# Zio_Qwiic_GPS_Module.net
KiCad netlist of a schematic drawn in EAGLE
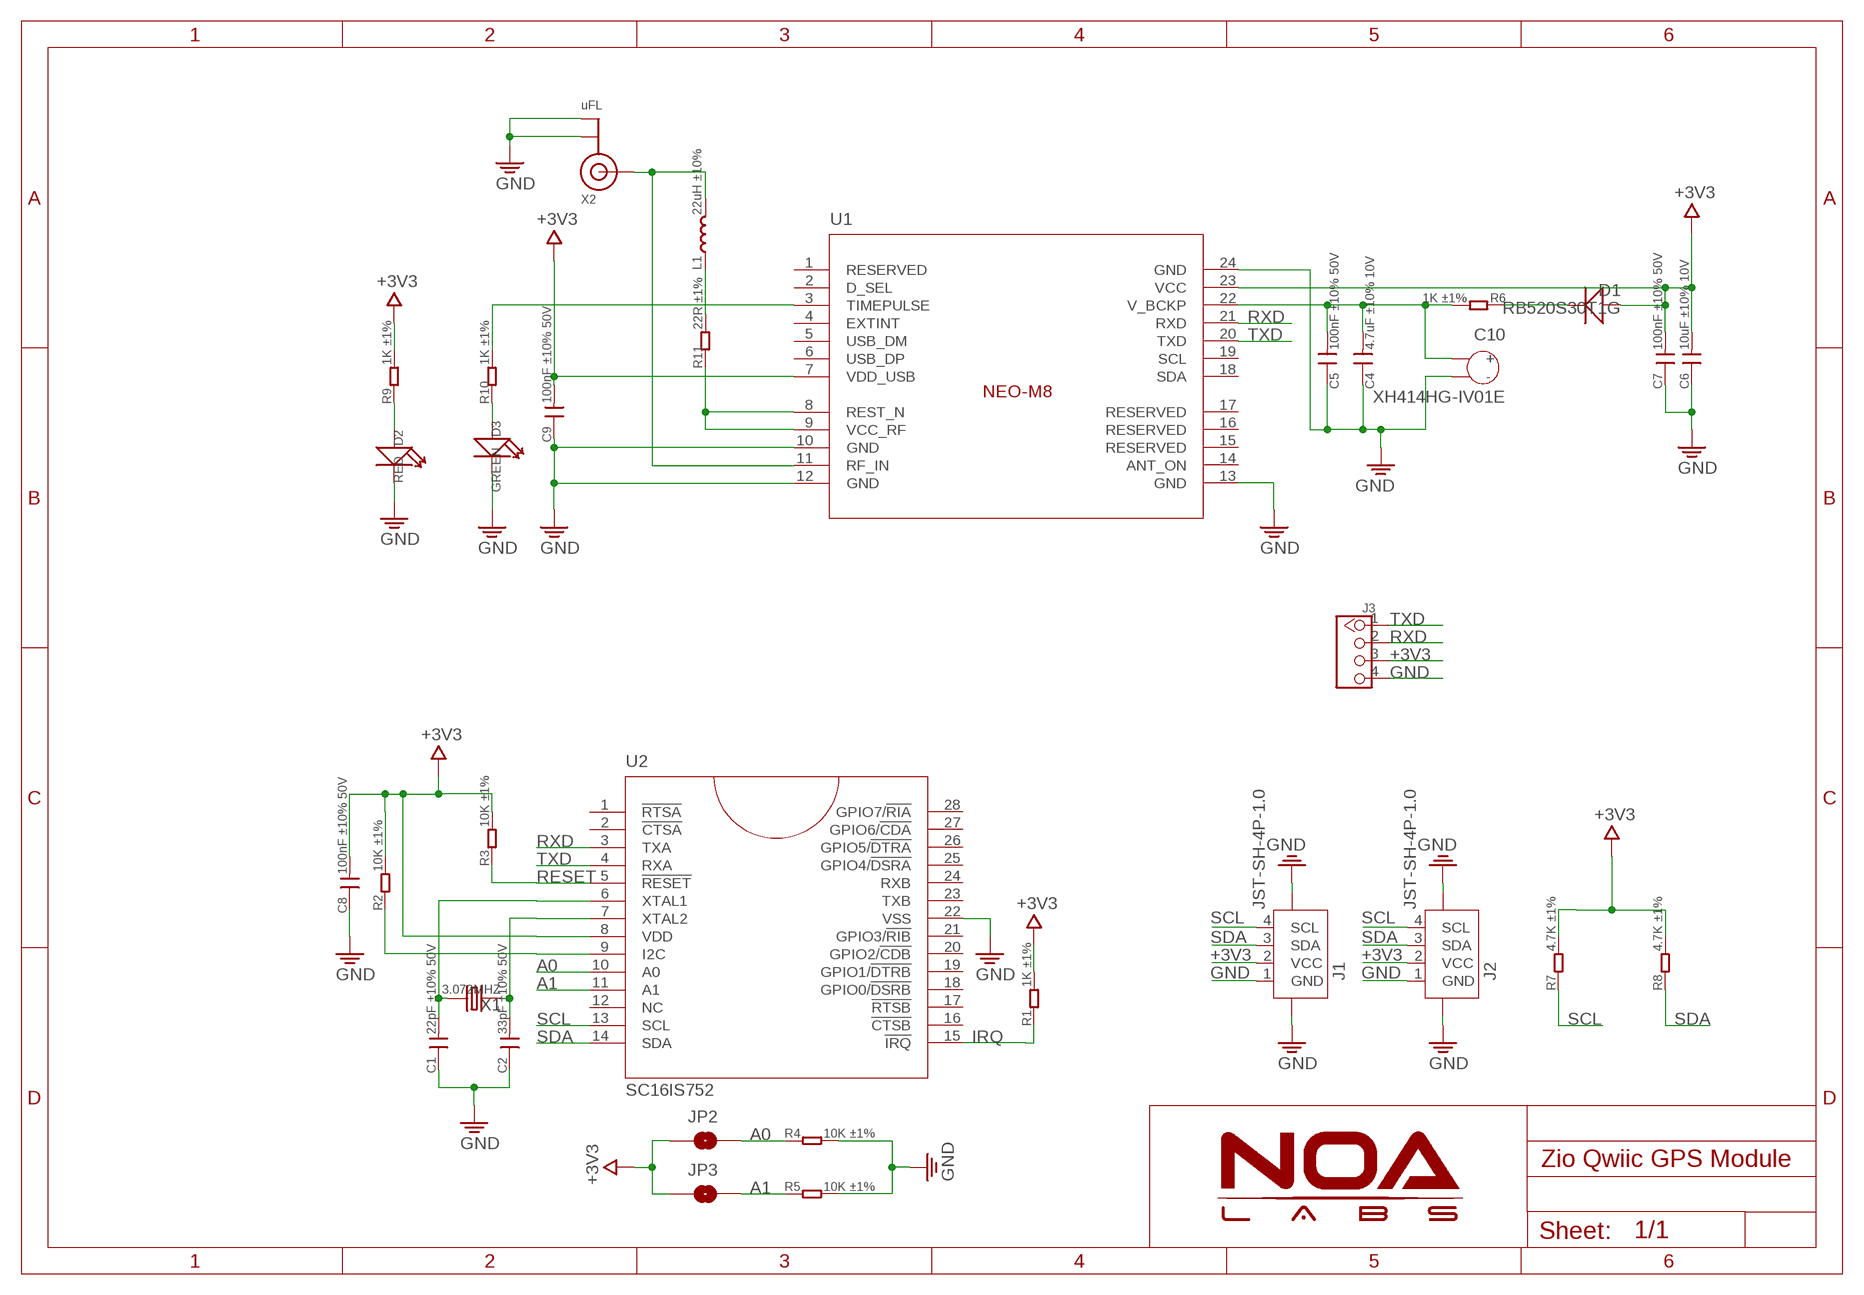
[diagram p0: schematic, sheet 1]

(export (version "E")
  (design (tool "Eeschema 10.0.6"))
  (components
    (comp (ref "C1")
      (value "22pF ±10% 50V")
      (footprint "eagle-import:C0603")
      (libsource (lib "eagle-import") (part "C-0603"))
    )
    (comp (ref "C2")
      (value "33pF ±10% 50V")
      (footprint "eagle-import:C0603")
      (libsource (lib "eagle-import") (part "C-0603"))
    )
    (comp (ref "C4")
      (value "4.7uF ±10% 10V")
      (footprint "eagle-import:C0603")
      (libsource (lib "eagle-import") (part "C-0603"))
    )
    (comp (ref "C5")
      (value "100nF ±10% 50V")
      (footprint "eagle-import:C0603")
      (libsource (lib "eagle-import") (part "C-0603"))
    )
    (comp (ref "C6")
      (value "10uF ±10% 10V")
      (footprint "eagle-import:C0603")
      (libsource (lib "eagle-import") (part "C-0603"))
    )
    (comp (ref "C7")
      (value "100nF ±10% 50V")
      (footprint "eagle-import:C0603")
      (libsource (lib "eagle-import") (part "C-0603"))
    )
    (comp (ref "C8")
      (value "100nF ±10% 50V")
      (footprint "eagle-import:C0603")
      (libsource (lib "eagle-import") (part "C-0603"))
    )
    (comp (ref "C9")
      (value "100nF ±10% 50V")
      (footprint "eagle-import:C0603")
      (libsource (lib "eagle-import") (part "C-0603"))
    )
    (comp (ref "C10")
      (value "XH414HG-IV01E")
      (footprint "eagle-import:XH414HG-IV01E")
      (libsource (lib "eagle-import") (part "XH414HG-IV01E"))
    )
    (comp (ref "D1")
      (value "RB520S30T1G")
      (footprint "eagle-import:SOD523")
      (libsource (lib "eagle-import") (part "D-0603"))
    )
    (comp (ref "D2")
      (value "RED")
      (footprint "eagle-import:LED-0603")
      (libsource (lib "eagle-import") (part "LED'0603'"))
    )
    (comp (ref "D3")
      (value "GREEN")
      (footprint "eagle-import:LED-0603")
      (libsource (lib "eagle-import") (part "LED'0603'"))
    )
    (comp (ref "J1")
      (value "JST-SH-4P-1.0")
      (footprint "eagle-import:JST-SH-4P")
      (libsource (lib "eagle-import") (part "JST-SH-4P-1.0"))
    )
    (comp (ref "J2")
      (value "JST-SH-4P-1.0")
      (footprint "eagle-import:JST-SH-4P")
      (libsource (lib "eagle-import") (part "JST-SH-4P-1.0"))
    )
    (comp (ref "J3")
      (value "HEADER-4P-1.25-SMD")
      (footprint "eagle-import:4PIN_SMD")
      (libsource (lib "eagle-import") (part "HEADER-4P-1.25-SMD"))
    )
    (comp (ref "JP2")
      (value "JUMPER-SMT_2_NC_PASTE_NOCREM")
      (footprint "eagle-import:SMT-JUMPER_2_NC_PASTE_SILK_NOCREM")
      (libsource (lib "eagle-import") (part "JUMPER-SMT_2_NC_PASTE_NOCREM"))
    )
    (comp (ref "JP3")
      (value "JUMPER-SMT_2_NC_PASTE_NOCREM")
      (footprint "eagle-import:SMT-JUMPER_2_NC_PASTE_SILK_NOCREM")
      (libsource (lib "eagle-import") (part "JUMPER-SMT_2_NC_PASTE_NOCREM"))
    )
    (comp (ref "L1")
      (value "22uH ±10%")
      (footprint "eagle-import:L0603")
      (libsource (lib "eagle-import") (part "L-0603"))
    )
    (comp (ref "R1")
      (value "1K ±1%")
      (footprint "eagle-import:R0603")
      (libsource (lib "eagle-import") (part "R-0603"))
    )
    (comp (ref "R2")
      (value "10K ±1%")
      (footprint "eagle-import:R0603")
      (libsource (lib "eagle-import") (part "R-0603"))
    )
    (comp (ref "R3")
      (value "10K ±1%")
      (footprint "eagle-import:R0603")
      (libsource (lib "eagle-import") (part "R-0603"))
    )
    (comp (ref "R4")
      (value "10K ±1%")
      (footprint "eagle-import:R0603")
      (libsource (lib "eagle-import") (part "R-0603"))
    )
    (comp (ref "R5")
      (value "10K ±1%")
      (footprint "eagle-import:R0603")
      (libsource (lib "eagle-import") (part "R-0603"))
    )
    (comp (ref "R6")
      (value "1K ±1%")
      (footprint "eagle-import:R0603")
      (libsource (lib "eagle-import") (part "R-0603"))
    )
    (comp (ref "R7")
      (value "4.7K ±1%")
      (footprint "eagle-import:R0603")
      (libsource (lib "eagle-import") (part "R-0603"))
    )
    (comp (ref "R8")
      (value "4.7K ±1%")
      (footprint "eagle-import:R0603")
      (libsource (lib "eagle-import") (part "R-0603"))
    )
    (comp (ref "R9")
      (value "1K ±1%")
      (footprint "eagle-import:R0603")
      (libsource (lib "eagle-import") (part "R-0603"))
    )
    (comp (ref "R10")
      (value "1K ±1%")
      (footprint "eagle-import:R0603")
      (libsource (lib "eagle-import") (part "R-0603"))
    )
    (comp (ref "R11")
      (value "22R ±1%")
      (footprint "eagle-import:R0603")
      (libsource (lib "eagle-import") (part "R-0603"))
    )
    (comp (ref "U1")
      (value "NEO-M8N")
      (footprint "eagle-import:NEO-M8N")
      (libsource (lib "eagle-import") (part "NEO-M8N"))
    )
    (comp (ref "U2")
      (value "SC16IS752")
      (footprint "eagle-import:TSSOP28")
      (libsource (lib "eagle-import") (part "SC16IS752"))
    )
    (comp (ref "X1")
      (value "3.072MHZ")
      (footprint "eagle-import:HC49_S")
      (libsource (lib "eagle-import") (part "CRYSTAL-HC49S"))
    )
    (comp (ref "X2")
      (value "uFL")
      (footprint "eagle-import:U.FL")
      (libsource (lib "eagle-import") (part "ANTENNA_U.FL"))
    )
  )
  (nets
    (net (code "1") (name "+3V3") (class "Default")
      (node (ref "C6") (pin "2") (pinfunction "2_2") (pintype "passive"))
      (node (ref "C7") (pin "2") (pinfunction "2_2") (pintype "passive"))
      (node (ref "C8") (pin "2") (pinfunction "2_2") (pintype "passive"))
      (node (ref "C9") (pin "2") (pinfunction "2_2") (pintype "passive"))
      (node (ref "D1") (pin "+") (pinfunction "+_+") (pintype "passive"))
      (node (ref "J1") (pin "2") (pinfunction "VCC_2") (pintype "bidirectional"))
      (node (ref "J2") (pin "2") (pinfunction "VCC_2") (pintype "bidirectional"))
      (node (ref "J3") (pin "3") (pinfunction "P$3_3") (pintype "bidirectional"))
      (node (ref "JP2") (pin "1") (pinfunction "1_1") (pintype "passive"))
      (node (ref "JP3") (pin "1") (pinfunction "1_1") (pintype "passive"))
      (node (ref "R1") (pin "2") (pinfunction "2_2") (pintype "passive"))
      (node (ref "R2") (pin "2") (pinfunction "2_2") (pintype "passive"))
      (node (ref "R3") (pin "2") (pinfunction "2_2") (pintype "passive"))
      (node (ref "R7") (pin "2") (pinfunction "2_2") (pintype "passive"))
      (node (ref "R8") (pin "2") (pinfunction "2_2") (pintype "passive"))
      (node (ref "R9") (pin "2") (pinfunction "2_2") (pintype "passive"))
      (node (ref "U1") (pin "23") (pinfunction "VCC_23") (pintype "bidirectional"))
      (node (ref "U1") (pin "7") (pinfunction "VDD_USB_7") (pintype "bidirectional"))
      (node (ref "U2") (pin "8") (pinfunction "VDD_8") (pintype "bidirectional"))
    )
    (net (code "2") (name "/A0") (class "Default")
      (node (ref "JP2") (pin "2") (pinfunction "2_2") (pintype "passive"))
      (node (ref "R4") (pin "1") (pinfunction "1_1") (pintype "passive"))
      (node (ref "U2") (pin "10") (pinfunction "A0_10") (pintype "bidirectional"))
    )
    (net (code "3") (name "/A1") (class "Default")
      (node (ref "JP3") (pin "2") (pinfunction "2_2") (pintype "passive"))
      (node (ref "R5") (pin "1") (pinfunction "1_1") (pintype "passive"))
      (node (ref "U2") (pin "11") (pinfunction "A1_11") (pintype "bidirectional"))
    )
    (net (code "4") (name "/IRQ") (class "Default")
      (node (ref "R1") (pin "1") (pinfunction "1_1") (pintype "passive"))
      (node (ref "U2") (pin "15") (pinfunction "~{IRQ}_15") (pintype "bidirectional"))
    )
    (net (code "5") (name "/RESET") (class "Default")
      (node (ref "R3") (pin "1") (pinfunction "1_1") (pintype "passive"))
      (node (ref "U2") (pin "5") (pinfunction "~{RESET}_5") (pintype "bidirectional"))
    )
    (net (code "6") (name "/RXD") (class "Default")
      (node (ref "J3") (pin "2") (pinfunction "P$2_2") (pintype "bidirectional"))
      (node (ref "U1") (pin "21") (pinfunction "RXD_21") (pintype "bidirectional"))
      (node (ref "U2") (pin "3") (pinfunction "TXA_3") (pintype "bidirectional"))
    )
    (net (code "7") (name "/SCL") (class "Default")
      (node (ref "J1") (pin "4") (pinfunction "SCL_4") (pintype "bidirectional"))
      (node (ref "J2") (pin "4") (pinfunction "SCL_4") (pintype "bidirectional"))
      (node (ref "R7") (pin "1") (pinfunction "1_1") (pintype "passive"))
      (node (ref "U2") (pin "13") (pinfunction "SCL_13") (pintype "bidirectional"))
    )
    (net (code "8") (name "/SDA") (class "Default")
      (node (ref "J1") (pin "3") (pinfunction "SDA_3") (pintype "bidirectional"))
      (node (ref "J2") (pin "3") (pinfunction "SDA_3") (pintype "bidirectional"))
      (node (ref "R8") (pin "1") (pinfunction "1_1") (pintype "passive"))
      (node (ref "U2") (pin "14") (pinfunction "SDA_14") (pintype "bidirectional"))
    )
    (net (code "9") (name "/TXD") (class "Default")
      (node (ref "J3") (pin "1") (pinfunction "P$1_1") (pintype "bidirectional"))
      (node (ref "U1") (pin "20") (pinfunction "TXD_20") (pintype "bidirectional"))
      (node (ref "U2") (pin "4") (pinfunction "RXA_4") (pintype "bidirectional"))
    )
    (net (code "10") (name "GND") (class "Default")
      (node (ref "C1") (pin "1") (pinfunction "1_1") (pintype "passive"))
      (node (ref "C10") (pin "-") (pinfunction "-_-") (pintype "bidirectional"))
      (node (ref "C2") (pin "1") (pinfunction "1_1") (pintype "passive"))
      (node (ref "C4") (pin "1") (pinfunction "1_1") (pintype "passive"))
      (node (ref "C5") (pin "1") (pinfunction "1_1") (pintype "passive"))
      (node (ref "C6") (pin "1") (pinfunction "1_1") (pintype "passive"))
      (node (ref "C7") (pin "1") (pinfunction "1_1") (pintype "passive"))
      (node (ref "C8") (pin "1") (pinfunction "1_1") (pintype "passive"))
      (node (ref "C9") (pin "1") (pinfunction "1_1") (pintype "passive"))
      (node (ref "D2") (pin "-") (pinfunction "-_-") (pintype "passive"))
      (node (ref "D3") (pin "-") (pinfunction "-_-") (pintype "passive"))
      (node (ref "J1") (pin "1") (pinfunction "GND_1") (pintype "bidirectional"))
      (node (ref "J1") (pin "NC1") (pinfunction "5_NC1") (pintype "bidirectional"))
      (node (ref "J1") (pin "NC2") (pinfunction "6_NC2") (pintype "bidirectional"))
      (node (ref "J2") (pin "1") (pinfunction "GND_1") (pintype "bidirectional"))
      (node (ref "J2") (pin "NC1") (pinfunction "5_NC1") (pintype "bidirectional"))
      (node (ref "J2") (pin "NC2") (pinfunction "6_NC2") (pintype "bidirectional"))
      (node (ref "J3") (pin "4") (pinfunction "P$4_4") (pintype "bidirectional"))
      (node (ref "R4") (pin "2") (pinfunction "2_2") (pintype "passive"))
      (node (ref "R5") (pin "2") (pinfunction "2_2") (pintype "passive"))
      (node (ref "U1") (pin "10") (pinfunction "GND_10") (pintype "bidirectional"))
      (node (ref "U1") (pin "12") (pinfunction "GND_12") (pintype "bidirectional"))
      (node (ref "U1") (pin "13") (pinfunction "GND_13") (pintype "bidirectional"))
      (node (ref "U1") (pin "24") (pinfunction "GND_24") (pintype "bidirectional"))
      (node (ref "U2") (pin "22") (pinfunction "VSS_22") (pintype "bidirectional"))
      (node (ref "X2") (pin "1") (pinfunction "GND_1") (pintype "passive"))
      (node (ref "X2") (pin "2") (pinfunction "GND_2") (pintype "passive"))
    )
    (net (code "11") (name "Net-(D1-Pad-)") (class "Default")
      (node (ref "D1") (pin "-") (pinfunction "-_-") (pintype "passive"))
      (node (ref "R6") (pin "1") (pinfunction "1_1") (pintype "passive"))
    )
    (net (code "12") (name "Net-(D2-Pad+)") (class "Default")
      (node (ref "D2") (pin "+") (pinfunction "+_+") (pintype "passive"))
      (node (ref "R9") (pin "1") (pinfunction "1_1") (pintype "passive"))
    )
    (net (code "13") (name "Net-(D3-Pad+)") (class "Default")
      (node (ref "D3") (pin "+") (pinfunction "+_+") (pintype "passive"))
      (node (ref "R10") (pin "1") (pinfunction "1_1") (pintype "passive"))
    )
    (net (code "14") (name "Net-(L1-Pad1)") (class "Default")
      (node (ref "L1") (pin "1") (pinfunction "1_1") (pintype "passive"))
      (node (ref "R11") (pin "2") (pinfunction "2_2") (pintype "passive"))
    )
    (net (code "15") (name "Net-(U1-REST_N)") (class "Default")
      (node (ref "R11") (pin "1") (pinfunction "1_1") (pintype "passive"))
      (node (ref "U1") (pin "8") (pinfunction "REST_N_8") (pintype "bidirectional"))
      (node (ref "U1") (pin "9") (pinfunction "VCC_RF_9") (pintype "bidirectional"))
    )
    (net (code "16") (name "Net-(U1-RF_IN)") (class "Default")
      (node (ref "L1") (pin "2") (pinfunction "2_2") (pintype "passive"))
      (node (ref "U1") (pin "11") (pinfunction "RF_IN_11") (pintype "bidirectional"))
      (node (ref "X2") (pin "3") (pinfunction "SIGNAL_3") (pintype "passive"))
    )
    (net (code "17") (name "Net-(U1-TIMEPULSE)") (class "Default")
      (node (ref "R10") (pin "2") (pinfunction "2_2") (pintype "passive"))
      (node (ref "U1") (pin "3") (pinfunction "TIMEPULSE_3") (pintype "bidirectional"))
    )
    (net (code "18") (name "Net-(U1-V_BCKP)") (class "Default")
      (node (ref "C10") (pin "+") (pinfunction "+_+") (pintype "bidirectional"))
      (node (ref "C4") (pin "2") (pinfunction "2_2") (pintype "passive"))
      (node (ref "C5") (pin "2") (pinfunction "2_2") (pintype "passive"))
      (node (ref "R6") (pin "2") (pinfunction "2_2") (pintype "passive"))
      (node (ref "U1") (pin "22") (pinfunction "V_BCKP_22") (pintype "bidirectional"))
    )
    (net (code "19") (name "Net-(U2-I2C)") (class "Default")
      (node (ref "R2") (pin "1") (pinfunction "1_1") (pintype "passive"))
      (node (ref "U2") (pin "9") (pinfunction "I2C_9") (pintype "bidirectional"))
    )
    (net (code "20") (name "Net-(U2-XTAL1)") (class "Default")
      (node (ref "C1") (pin "2") (pinfunction "2_2") (pintype "passive"))
      (node (ref "U2") (pin "6") (pinfunction "XTAL1_6") (pintype "bidirectional"))
      (node (ref "X1") (pin "2") (pinfunction "2_2") (pintype "passive"))
    )
    (net (code "21") (name "Net-(U2-XTAL2)") (class "Default")
      (node (ref "C2") (pin "2") (pinfunction "2_2") (pintype "passive"))
      (node (ref "U2") (pin "7") (pinfunction "XTAL2_7") (pintype "bidirectional"))
      (node (ref "X1") (pin "1") (pinfunction "1_1") (pintype "passive"))
    )
    (net (code "22") (name "unconnected-(U1-ANT_ON-Pad14)") (class "Default")
      (node (ref "U1") (pin "14") (pinfunction "ANT_ON_14") (pintype "bidirectional"))
    )
    (net (code "23") (name "unconnected-(U1-D_SEL-Pad2)") (class "Default")
      (node (ref "U1") (pin "2") (pinfunction "D_SEL_2") (pintype "bidirectional"))
    )
    (net (code "24") (name "unconnected-(U1-EXTINT-Pad4)") (class "Default")
      (node (ref "U1") (pin "4") (pinfunction "EXTINT_4") (pintype "bidirectional"))
    )
    (net (code "25") (name "unconnected-(U1-RESERVED-Pad1)") (class "Default")
      (node (ref "U1") (pin "1") (pinfunction "RESERVED_1") (pintype "bidirectional"))
    )
    (net (code "26") (name "unconnected-(U1-RESERVED-Pad15)") (class "Default")
      (node (ref "U1") (pin "15") (pinfunction "RESERVED_15") (pintype "bidirectional"))
    )
    (net (code "27") (name "unconnected-(U1-RESERVED-Pad16)") (class "Default")
      (node (ref "U1") (pin "16") (pinfunction "RESERVED_16") (pintype "bidirectional"))
    )
    (net (code "28") (name "unconnected-(U1-RESERVED-Pad17)") (class "Default")
      (node (ref "U1") (pin "17") (pinfunction "RESERVED_17") (pintype "bidirectional"))
    )
    (net (code "29") (name "unconnected-(U1-SCL-Pad19)") (class "Default")
      (node (ref "U1") (pin "19") (pinfunction "SCL_19") (pintype "bidirectional"))
    )
    (net (code "30") (name "unconnected-(U1-SDA-Pad18)") (class "Default")
      (node (ref "U1") (pin "18") (pinfunction "SDA_18") (pintype "bidirectional"))
    )
    (net (code "31") (name "unconnected-(U1-USB_DM-Pad5)") (class "Default")
      (node (ref "U1") (pin "5") (pinfunction "USB_DM_5") (pintype "bidirectional"))
    )
    (net (code "32") (name "unconnected-(U1-USB_DP-Pad6)") (class "Default")
      (node (ref "U1") (pin "6") (pinfunction "USB_DP_6") (pintype "bidirectional"))
    )
    (net (code "33") (name "unconnected-(U2-GPIO0{slash}~{DSRB}-Pad18)") (class "Default")
      (node (ref "U2") (pin "18") (pinfunction "GPIO0/~{DSRB}_18") (pintype "bidirectional"))
    )
    (net (code "34") (name "unconnected-(U2-GPIO1{slash}~{DTRB}-Pad19)") (class "Default")
      (node (ref "U2") (pin "19") (pinfunction "GPIO1/~{DTRB}_19") (pintype "bidirectional"))
    )
    (net (code "35") (name "unconnected-(U2-GPIO2{slash}~{CDB}-Pad20)") (class "Default")
      (node (ref "U2") (pin "20") (pinfunction "GPIO2/~{CDB}_20") (pintype "bidirectional"))
    )
    (net (code "36") (name "unconnected-(U2-GPIO3{slash}~{RIB}-Pad21)") (class "Default")
      (node (ref "U2") (pin "21") (pinfunction "GPIO3/~{RIB}_21") (pintype "bidirectional"))
    )
    (net (code "37") (name "unconnected-(U2-GPIO4{slash}~{DSRA}-Pad25)") (class "Default")
      (node (ref "U2") (pin "25") (pinfunction "GPIO4/~{DSRA}_25") (pintype "bidirectional"))
    )
    (net (code "38") (name "unconnected-(U2-GPIO5{slash}~{DTRA}-Pad26)") (class "Default")
      (node (ref "U2") (pin "26") (pinfunction "GPIO5/~{DTRA}_26") (pintype "bidirectional"))
    )
    (net (code "39") (name "unconnected-(U2-GPIO6{slash}~{CDA}-Pad27)") (class "Default")
      (node (ref "U2") (pin "27") (pinfunction "GPIO6/~{CDA}_27") (pintype "bidirectional"))
    )
    (net (code "40") (name "unconnected-(U2-GPIO7{slash}~{RIA}-Pad28)") (class "Default")
      (node (ref "U2") (pin "28") (pinfunction "GPIO7/~{RIA}_28") (pintype "bidirectional"))
    )
    (net (code "41") (name "unconnected-(U2-NC-Pad12)") (class "Default")
      (node (ref "U2") (pin "12") (pinfunction "NC_12") (pintype "bidirectional"))
    )
    (net (code "42") (name "unconnected-(U2-RXB-Pad24)") (class "Default")
      (node (ref "U2") (pin "24") (pinfunction "RXB_24") (pintype "bidirectional"))
    )
    (net (code "43") (name "unconnected-(U2-TXB-Pad23)") (class "Default")
      (node (ref "U2") (pin "23") (pinfunction "TXB_23") (pintype "bidirectional"))
    )
    (net (code "44") (name "unconnected-(U2-~{CTSA}-Pad2)") (class "Default")
      (node (ref "U2") (pin "2") (pinfunction "~{CTSA}_2") (pintype "bidirectional"))
    )
    (net (code "45") (name "unconnected-(U2-~{CTSB}-Pad16)") (class "Default")
      (node (ref "U2") (pin "16") (pinfunction "~{CTSB}_16") (pintype "bidirectional"))
    )
    (net (code "46") (name "unconnected-(U2-~{RTSA}-Pad1)") (class "Default")
      (node (ref "U2") (pin "1") (pinfunction "~{RTSA}_1") (pintype "bidirectional"))
    )
    (net (code "47") (name "unconnected-(U2-~{RTSB}-Pad17)") (class "Default")
      (node (ref "U2") (pin "17") (pinfunction "~{RTSB}_17") (pintype "bidirectional"))
    )
  )
)
